# 20170814_DukeExperimentalHeadstageAmplif.net
KiCad netlist of a schematic drawn in EAGLE
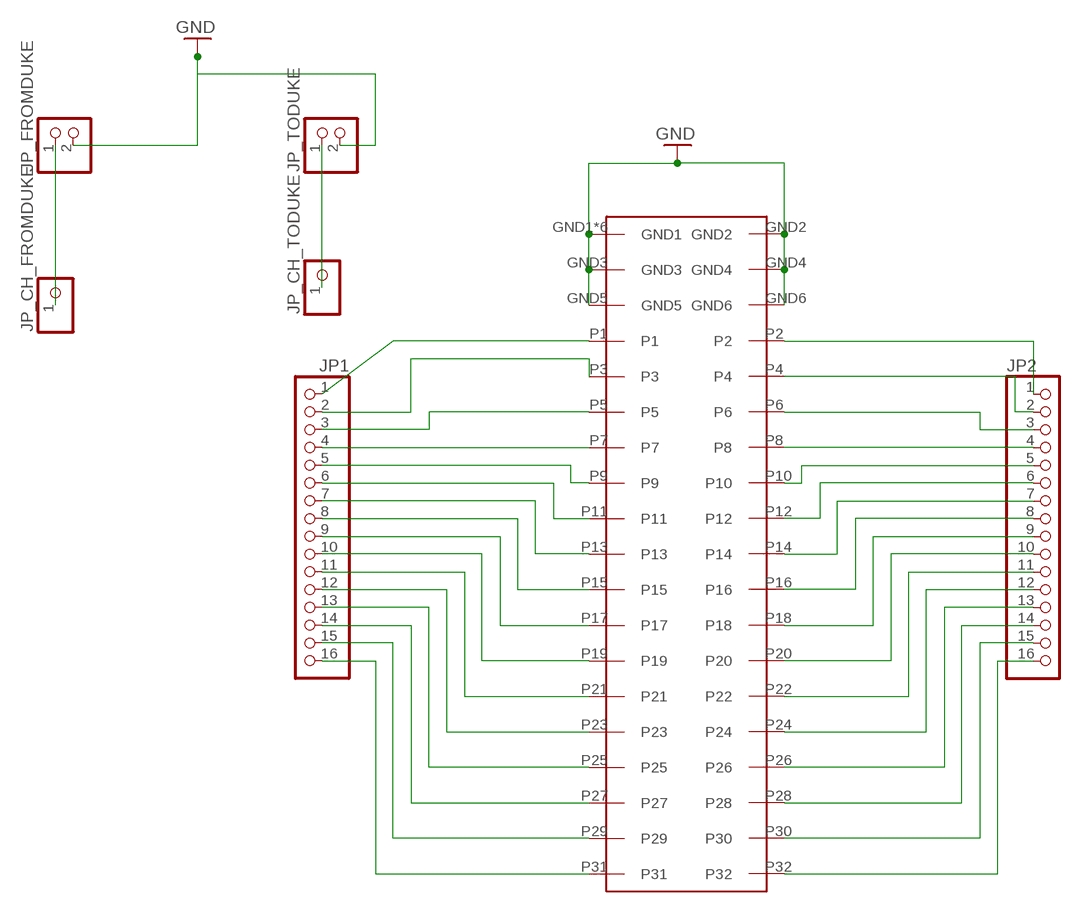
[diagram p0: schematic, sheet 1]

(export (version "E")
  (design (tool "Eeschema 10.0.6"))
  (components
    (comp (ref "JP1")
      (value "PINHD-1X16")
      (footprint "eagle-import:1X16")
      (libsource (lib "eagle-import") (part "PINHD-1X16"))
    )
    (comp (ref "JP2")
      (value "PINHD-1X16")
      (footprint "eagle-import:1X16")
      (libsource (lib "eagle-import") (part "PINHD-1X16"))
    )
    (comp (ref "JP_CH_FROMDUKE")
      (value "PINHD-1X1")
      (footprint "eagle-import:1X01")
      (libsource (lib "eagle-import") (part "PINHD-1X1"))
    )
    (comp (ref "JP_CH_TODUKE")
      (value "PINHD-1X1")
      (footprint "eagle-import:1X01")
      (libsource (lib "eagle-import") (part "PINHD-1X1"))
    )
    (comp (ref "JP_FROMDUKE")
      (value "PINHD-1X2")
      (footprint "eagle-import:1X02")
      (libsource (lib "eagle-import") (part "PINHD-1X2"))
    )
    (comp (ref "JP_TODUKE")
      (value "PINHD-1X2")
      (footprint "eagle-import:1X02")
      (libsource (lib "eagle-import") (part "PINHD-1X2"))
    )
    (comp (ref "U$1")
      (value "MIS-019-01-H-D")
      (footprint "eagle-import:MIS-019-01-H-D")
      (libsource (lib "eagle-import") (part "MIS-019-01-H-D"))
    )
  )
  (nets
    (net (code "1") (name "GND") (class "Default")
      (node (ref "JP_FROMDUKE") (pin "2") (pinfunction "2_2") (pintype "passive"))
      (node (ref "JP_TODUKE") (pin "2") (pinfunction "2_2") (pintype "passive"))
      (node (ref "U$1") (pin "GND1") (pinfunction "GND1_GND1") (pintype "bidirectional"))
      (node (ref "U$1") (pin "GND2") (pinfunction "GND2_GND2") (pintype "bidirectional"))
      (node (ref "U$1") (pin "GND3") (pinfunction "GND3_GND3") (pintype "bidirectional"))
      (node (ref "U$1") (pin "GND4") (pinfunction "GND4_GND4") (pintype "bidirectional"))
      (node (ref "U$1") (pin "GND5") (pinfunction "GND5_GND5") (pintype "bidirectional"))
      (node (ref "U$1") (pin "GND6") (pinfunction "GND6_GND6") (pintype "bidirectional"))
      (node (ref "U$1") (pin "SH1") (pinfunction "GND1_SH1") (pintype "bidirectional"))
      (node (ref "U$1") (pin "SH2") (pinfunction "GND1_SH2") (pintype "bidirectional"))
      (node (ref "U$1") (pin "SH3") (pinfunction "GND1_SH3") (pintype "bidirectional"))
      (node (ref "U$1") (pin "SH4") (pinfunction "GND1_SH4") (pintype "bidirectional"))
      (node (ref "U$1") (pin "SH5") (pinfunction "GND1_SH5") (pintype "bidirectional"))
    )
    (net (code "2") (name "Net-(JP1-Pad1)") (class "Default")
      (node (ref "JP1") (pin "1") (pinfunction "1_1") (pintype "passive"))
      (node (ref "U$1") (pin "P1") (pinfunction "P1_P1") (pintype "bidirectional"))
    )
    (net (code "3") (name "Net-(JP1-Pad2)") (class "Default")
      (node (ref "JP1") (pin "2") (pinfunction "2_2") (pintype "passive"))
      (node (ref "U$1") (pin "P3") (pinfunction "P3_P3") (pintype "bidirectional"))
    )
    (net (code "4") (name "Net-(JP1-Pad3)") (class "Default")
      (node (ref "JP1") (pin "3") (pinfunction "3_3") (pintype "passive"))
      (node (ref "U$1") (pin "P5") (pinfunction "P5_P5") (pintype "bidirectional"))
    )
    (net (code "5") (name "Net-(JP1-Pad4)") (class "Default")
      (node (ref "JP1") (pin "4") (pinfunction "4_4") (pintype "passive"))
      (node (ref "U$1") (pin "P7") (pinfunction "P7_P7") (pintype "bidirectional"))
    )
    (net (code "6") (name "Net-(JP1-Pad5)") (class "Default")
      (node (ref "JP1") (pin "5") (pinfunction "5_5") (pintype "passive"))
      (node (ref "U$1") (pin "P9") (pinfunction "P9_P9") (pintype "bidirectional"))
    )
    (net (code "7") (name "Net-(JP1-Pad6)") (class "Default")
      (node (ref "JP1") (pin "6") (pinfunction "6_6") (pintype "passive"))
      (node (ref "U$1") (pin "P11") (pinfunction "P11_P11") (pintype "bidirectional"))
    )
    (net (code "8") (name "Net-(JP1-Pad7)") (class "Default")
      (node (ref "JP1") (pin "7") (pinfunction "7_7") (pintype "passive"))
      (node (ref "U$1") (pin "P13") (pinfunction "P13_P13") (pintype "bidirectional"))
    )
    (net (code "9") (name "Net-(JP1-Pad8)") (class "Default")
      (node (ref "JP1") (pin "8") (pinfunction "8_8") (pintype "passive"))
      (node (ref "U$1") (pin "P15") (pinfunction "P15_P15") (pintype "bidirectional"))
    )
    (net (code "10") (name "Net-(JP1-Pad9)") (class "Default")
      (node (ref "JP1") (pin "9") (pinfunction "9_9") (pintype "passive"))
      (node (ref "U$1") (pin "P17") (pinfunction "P17_P17") (pintype "bidirectional"))
    )
    (net (code "11") (name "Net-(JP1-Pad10)") (class "Default")
      (node (ref "JP1") (pin "10") (pinfunction "10_10") (pintype "passive"))
      (node (ref "U$1") (pin "P19") (pinfunction "P19_P19") (pintype "bidirectional"))
    )
    (net (code "12") (name "Net-(JP1-Pad11)") (class "Default")
      (node (ref "JP1") (pin "11") (pinfunction "11_11") (pintype "passive"))
      (node (ref "U$1") (pin "P21") (pinfunction "P21_P21") (pintype "bidirectional"))
    )
    (net (code "13") (name "Net-(JP1-Pad12)") (class "Default")
      (node (ref "JP1") (pin "12") (pinfunction "12_12") (pintype "passive"))
      (node (ref "U$1") (pin "P23") (pinfunction "P23_P23") (pintype "bidirectional"))
    )
    (net (code "14") (name "Net-(JP1-Pad13)") (class "Default")
      (node (ref "JP1") (pin "13") (pinfunction "13_13") (pintype "passive"))
      (node (ref "U$1") (pin "P25") (pinfunction "P25_P25") (pintype "bidirectional"))
    )
    (net (code "15") (name "Net-(JP1-Pad14)") (class "Default")
      (node (ref "JP1") (pin "14") (pinfunction "14_14") (pintype "passive"))
      (node (ref "U$1") (pin "P27") (pinfunction "P27_P27") (pintype "bidirectional"))
    )
    (net (code "16") (name "Net-(JP1-Pad15)") (class "Default")
      (node (ref "JP1") (pin "15") (pinfunction "15_15") (pintype "passive"))
      (node (ref "U$1") (pin "P29") (pinfunction "P29_P29") (pintype "bidirectional"))
    )
    (net (code "17") (name "Net-(JP1-Pad16)") (class "Default")
      (node (ref "JP1") (pin "16") (pinfunction "16_16") (pintype "passive"))
      (node (ref "U$1") (pin "P31") (pinfunction "P31_P31") (pintype "bidirectional"))
    )
    (net (code "18") (name "Net-(JP2-Pad1)") (class "Default")
      (node (ref "JP2") (pin "1") (pinfunction "1_1") (pintype "passive"))
      (node (ref "U$1") (pin "P2") (pinfunction "P2_P2") (pintype "bidirectional"))
    )
    (net (code "19") (name "Net-(JP2-Pad2)") (class "Default")
      (node (ref "JP2") (pin "2") (pinfunction "2_2") (pintype "passive"))
      (node (ref "U$1") (pin "P4") (pinfunction "P4_P4") (pintype "bidirectional"))
    )
    (net (code "20") (name "Net-(JP2-Pad3)") (class "Default")
      (node (ref "JP2") (pin "3") (pinfunction "3_3") (pintype "passive"))
      (node (ref "U$1") (pin "P6") (pinfunction "P6_P6") (pintype "bidirectional"))
    )
    (net (code "21") (name "Net-(JP2-Pad4)") (class "Default")
      (node (ref "JP2") (pin "4") (pinfunction "4_4") (pintype "passive"))
      (node (ref "U$1") (pin "P8") (pinfunction "P8_P8") (pintype "bidirectional"))
    )
    (net (code "22") (name "Net-(JP2-Pad5)") (class "Default")
      (node (ref "JP2") (pin "5") (pinfunction "5_5") (pintype "passive"))
      (node (ref "U$1") (pin "P10") (pinfunction "P10_P10") (pintype "bidirectional"))
    )
    (net (code "23") (name "Net-(JP2-Pad6)") (class "Default")
      (node (ref "JP2") (pin "6") (pinfunction "6_6") (pintype "passive"))
      (node (ref "U$1") (pin "P12") (pinfunction "P12_P12") (pintype "bidirectional"))
    )
    (net (code "24") (name "Net-(JP2-Pad7)") (class "Default")
      (node (ref "JP2") (pin "7") (pinfunction "7_7") (pintype "passive"))
      (node (ref "U$1") (pin "P14") (pinfunction "P14_P14") (pintype "bidirectional"))
    )
    (net (code "25") (name "Net-(JP2-Pad8)") (class "Default")
      (node (ref "JP2") (pin "8") (pinfunction "8_8") (pintype "passive"))
      (node (ref "U$1") (pin "P16") (pinfunction "P16_P16") (pintype "bidirectional"))
    )
    (net (code "26") (name "Net-(JP2-Pad9)") (class "Default")
      (node (ref "JP2") (pin "9") (pinfunction "9_9") (pintype "passive"))
      (node (ref "U$1") (pin "P18") (pinfunction "P18_P18") (pintype "bidirectional"))
    )
    (net (code "27") (name "Net-(JP2-Pad10)") (class "Default")
      (node (ref "JP2") (pin "10") (pinfunction "10_10") (pintype "passive"))
      (node (ref "U$1") (pin "P20") (pinfunction "P20_P20") (pintype "bidirectional"))
    )
    (net (code "28") (name "Net-(JP2-Pad11)") (class "Default")
      (node (ref "JP2") (pin "11") (pinfunction "11_11") (pintype "passive"))
      (node (ref "U$1") (pin "P22") (pinfunction "P22_P22") (pintype "bidirectional"))
    )
    (net (code "29") (name "Net-(JP2-Pad12)") (class "Default")
      (node (ref "JP2") (pin "12") (pinfunction "12_12") (pintype "passive"))
      (node (ref "U$1") (pin "P24") (pinfunction "P24_P24") (pintype "bidirectional"))
    )
    (net (code "30") (name "Net-(JP2-Pad13)") (class "Default")
      (node (ref "JP2") (pin "13") (pinfunction "13_13") (pintype "passive"))
      (node (ref "U$1") (pin "P26") (pinfunction "P26_P26") (pintype "bidirectional"))
    )
    (net (code "31") (name "Net-(JP2-Pad14)") (class "Default")
      (node (ref "JP2") (pin "14") (pinfunction "14_14") (pintype "passive"))
      (node (ref "U$1") (pin "P28") (pinfunction "P28_P28") (pintype "bidirectional"))
    )
    (net (code "32") (name "Net-(JP2-Pad15)") (class "Default")
      (node (ref "JP2") (pin "15") (pinfunction "15_15") (pintype "passive"))
      (node (ref "U$1") (pin "P30") (pinfunction "P30_P30") (pintype "bidirectional"))
    )
    (net (code "33") (name "Net-(JP2-Pad16)") (class "Default")
      (node (ref "JP2") (pin "16") (pinfunction "16_16") (pintype "passive"))
      (node (ref "U$1") (pin "P32") (pinfunction "P32_P32") (pintype "bidirectional"))
    )
    (net (code "34") (name "Net-(JP_CH_FROMDUKE-Pad1)") (class "Default")
      (node (ref "JP_CH_FROMDUKE") (pin "1") (pinfunction "1_1") (pintype "passive"))
      (node (ref "JP_FROMDUKE") (pin "1") (pinfunction "1_1") (pintype "passive"))
    )
    (net (code "35") (name "Net-(JP_CH_TODUKE-Pad1)") (class "Default")
      (node (ref "JP_CH_TODUKE") (pin "1") (pinfunction "1_1") (pintype "passive"))
      (node (ref "JP_TODUKE") (pin "1") (pinfunction "1_1") (pintype "passive"))
    )
  )
)
